# SMART_LOCK_UK.net
KiCad netlist of a schematic drawn in EAGLE
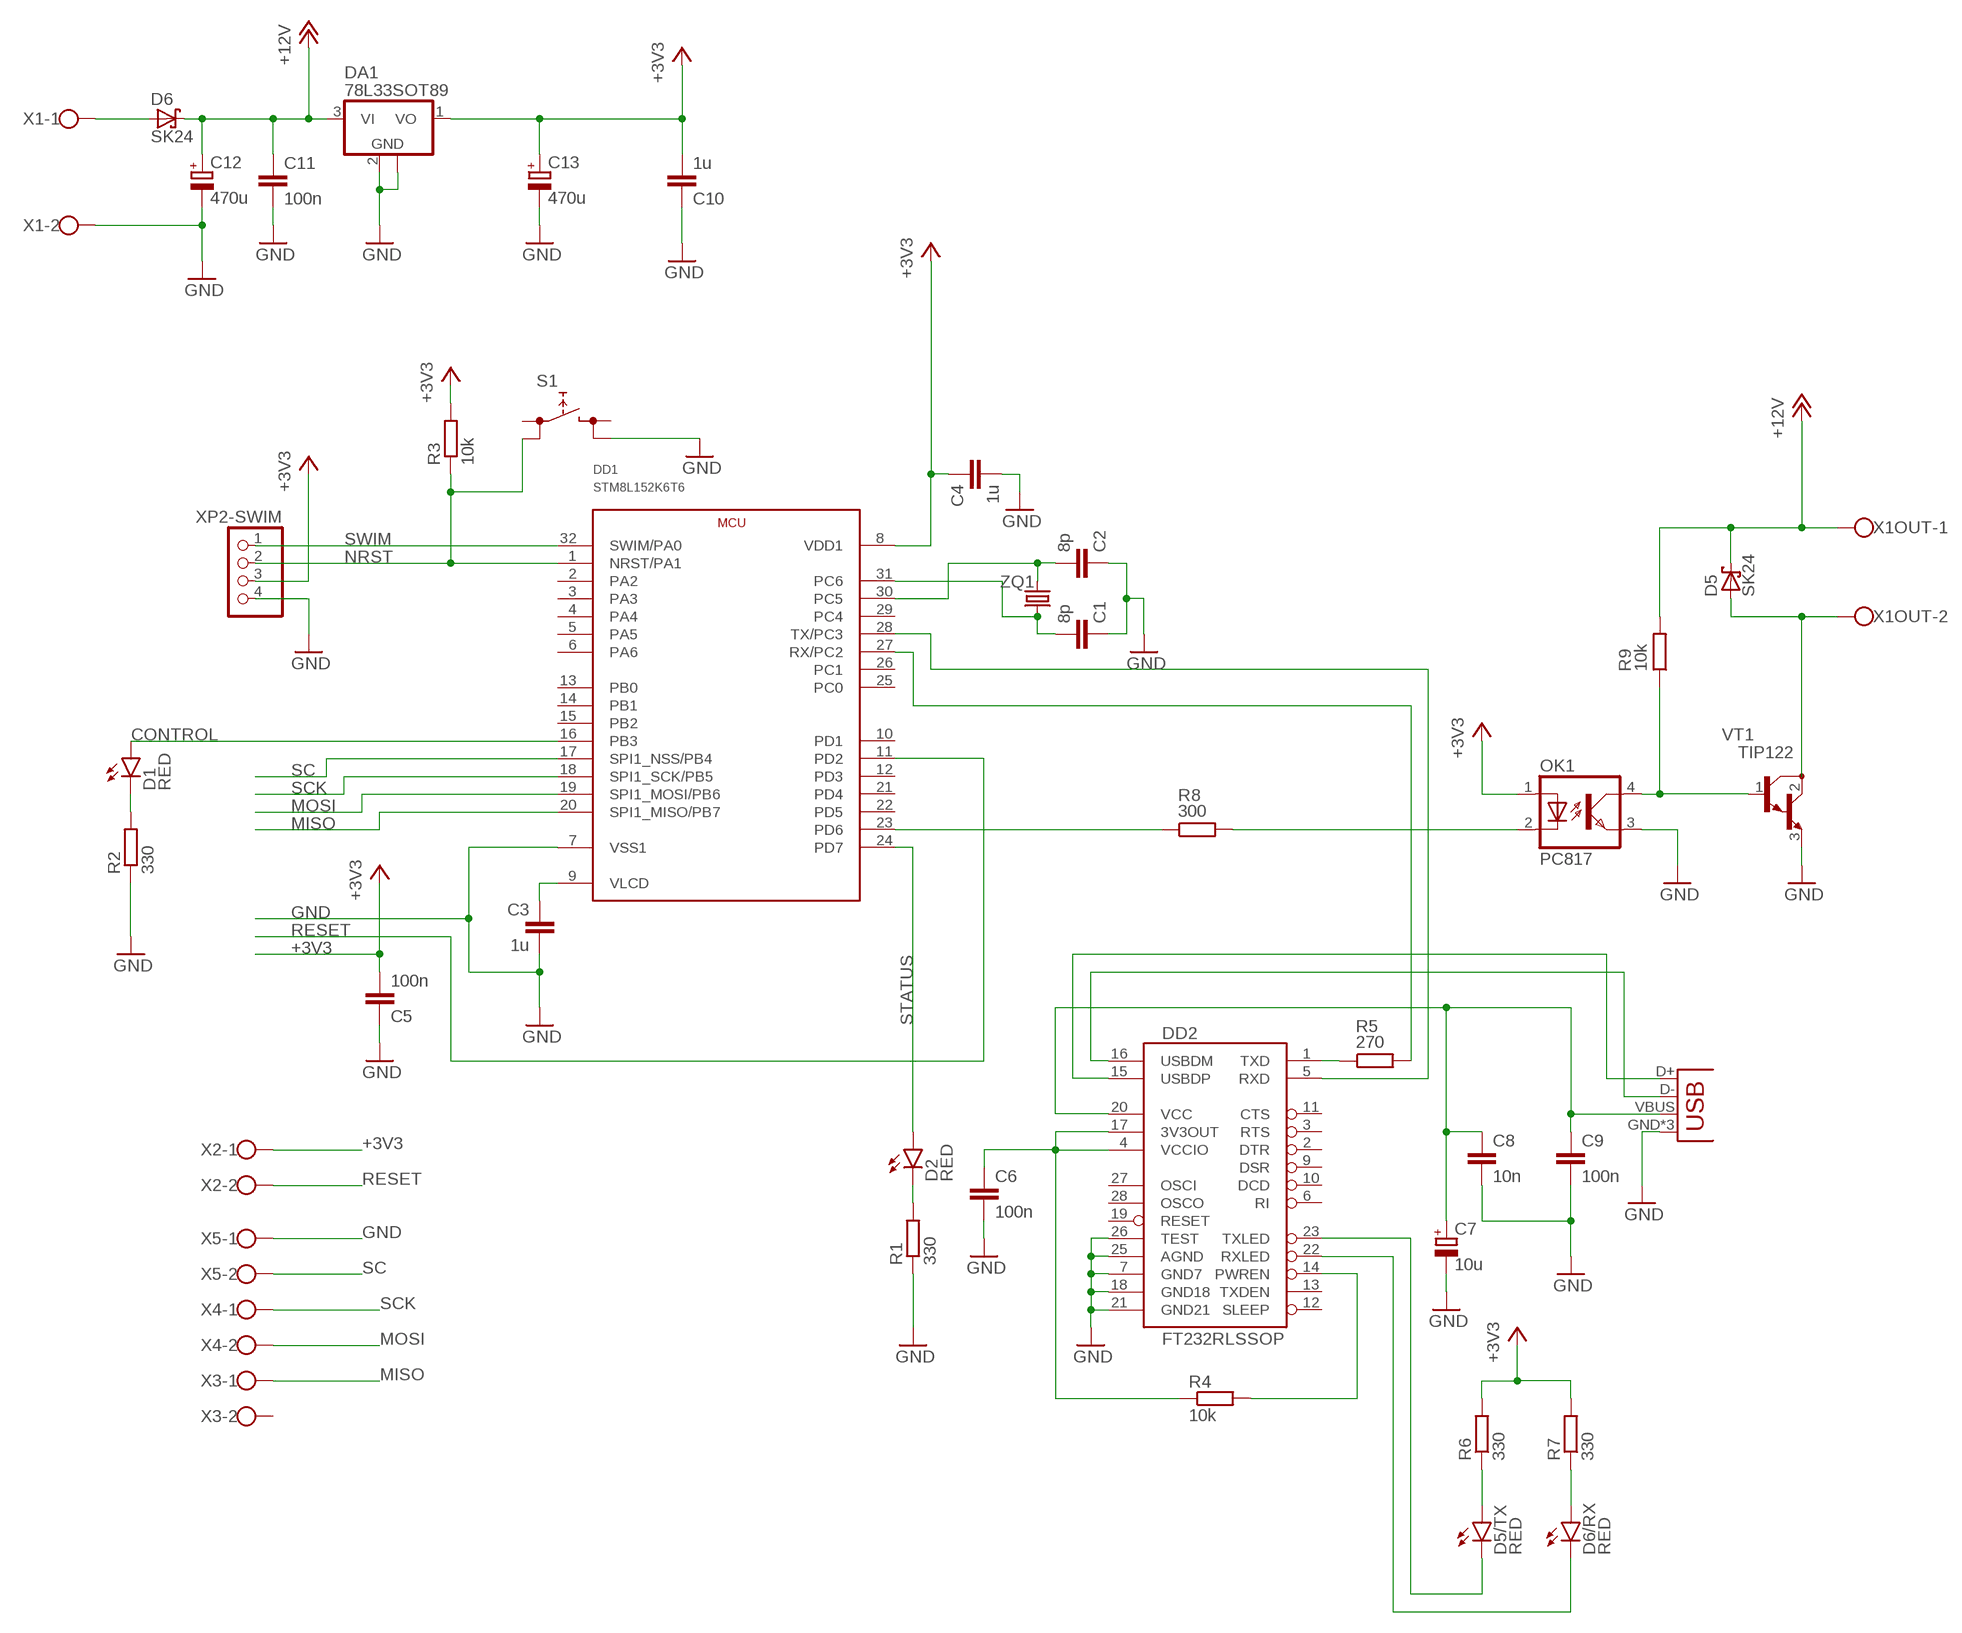
[diagram p0: schematic, sheet 1]

(export (version "E")
  (design (tool "Eeschema 10.0.6"))
  (components
    (comp (ref "C1")
      (value "8p")
      (footprint "eagle-import:C1206")
      (libsource (lib "eagle-import") (part "SMART LOCK UK_C-EUC1206"))
    )
    (comp (ref "C2")
      (value "8p")
      (footprint "eagle-import:C1206")
      (libsource (lib "eagle-import") (part "SMART LOCK UK_C-EUC1206"))
    )
    (comp (ref "C3")
      (value "1u")
      (footprint "eagle-import:C1206")
      (libsource (lib "eagle-import") (part "SMART LOCK UK_C-EUC1206"))
    )
    (comp (ref "C4")
      (value "1u")
      (footprint "eagle-import:C1206")
      (libsource (lib "eagle-import") (part "SMART LOCK UK_C-EUC1206"))
    )
    (comp (ref "C5")
      (value "100n")
      (footprint "eagle-import:C1206")
      (libsource (lib "eagle-import") (part "SMART LOCK UK_C-EUC1206"))
    )
    (comp (ref "C6")
      (value "100n")
      (footprint "eagle-import:C1206")
      (libsource (lib "eagle-import") (part "C-EUC1206"))
    )
    (comp (ref "C7")
      (value "10u")
      (footprint "eagle-import:E2,5-5")
      (libsource (lib "eagle-import") (part "CPOL-EUE2,5-5"))
    )
    (comp (ref "C8")
      (value "10n")
      (footprint "eagle-import:C1206")
      (libsource (lib "eagle-import") (part "C-EUC1206"))
    )
    (comp (ref "C9")
      (value "100n")
      (footprint "eagle-import:C1206")
      (libsource (lib "eagle-import") (part "C-EUC1206"))
    )
    (comp (ref "C10")
      (value "1u")
      (footprint "eagle-import:C1206")
      (libsource (lib "eagle-import") (part "SMART LOCK UK_C-EUC1206"))
    )
    (comp (ref "C11")
      (value "100n")
      (footprint "eagle-import:C1206")
      (libsource (lib "eagle-import") (part "C-EUC1206"))
    )
    (comp (ref "C12")
      (value "470u")
      (footprint "eagle-import:E3,5-8")
      (libsource (lib "eagle-import") (part "CPOL-EUE3,5-8"))
    )
    (comp (ref "C13")
      (value "470u")
      (footprint "eagle-import:E3,5-8")
      (libsource (lib "eagle-import") (part "CPOL-EUE3,5-8"))
    )
    (comp (ref "D1")
      (value "RED")
      (footprint "eagle-import:LED-1206")
      (libsource (lib "eagle-import") (part "LED-RED1206"))
    )
    (comp (ref "D2")
      (value "RED")
      (footprint "eagle-import:LED-1206")
      (libsource (lib "eagle-import") (part "LED-RED1206"))
    )
    (comp (ref "D5")
      (value "SK24")
      (footprint "eagle-import:SMB")
      (libsource (lib "eagle-import") (part "SCHOTTKY-DIODESMD"))
    )
    (comp (ref "D5/TX")
      (value "RED")
      (footprint "eagle-import:LED-1206")
      (libsource (lib "eagle-import") (part "LED-RED1206"))
    )
    (comp (ref "D6")
      (value "SK24")
      (footprint "eagle-import:SMB")
      (libsource (lib "eagle-import") (part "SCHOTTKY-DIODESMD"))
    )
    (comp (ref "D6/RX")
      (value "RED")
      (footprint "eagle-import:LED-1206")
      (libsource (lib "eagle-import") (part "LED-RED1206"))
    )
    (comp (ref "DA1")
      (value "78L33SOT89")
      (footprint "eagle-import:SOT89")
      (libsource (lib "eagle-import") (part "78L33SOT89"))
    )
    (comp (ref "DD1")
      (value "STM8L152K6T6")
      (footprint "eagle-import:LQFP32-7X7")
      (libsource (lib "eagle-import") (part "STM8L152K6T6"))
    )
    (comp (ref "DD2")
      (value "FT232RLSSOP")
      (footprint "eagle-import:SSOP28DB")
      (libsource (lib "eagle-import") (part "FT232RLSSOP"))
    )
    (comp (ref "JP1")
      (value "USB-B")
      (footprint "eagle-import:USB-B-PTH")
      (libsource (lib "eagle-import") (part "USB-B-CROW"))
    )
    (comp (ref "OK1")
      (value "PC817")
      (footprint "eagle-import:DIL04")
      (fields (field (name "MPN") "PC817X4J000F"))
      (libsource (lib "eagle-import") (part "PC817"))
    )
    (comp (ref "R1")
      (value "330")
      (footprint "eagle-import:M1206")
      (libsource (lib "eagle-import") (part "R-EU_LM1206"))
    )
    (comp (ref "R2")
      (value "330")
      (footprint "eagle-import:M1206")
      (libsource (lib "eagle-import") (part "R-EU_LM1206"))
    )
    (comp (ref "R3")
      (value "10k")
      (footprint "eagle-import:M1206")
      (libsource (lib "eagle-import") (part "R-EU_LM1206"))
    )
    (comp (ref "R4")
      (value "10k")
      (footprint "eagle-import:M1206")
      (libsource (lib "eagle-import") (part "R-EUM1206"))
    )
    (comp (ref "R5")
      (value "270")
      (footprint "eagle-import:M1206")
      (libsource (lib "eagle-import") (part "R-EUM1206"))
    )
    (comp (ref "R6")
      (value "330")
      (footprint "eagle-import:M1206")
      (libsource (lib "eagle-import") (part "R-EU_LM1206"))
    )
    (comp (ref "R7")
      (value "330")
      (footprint "eagle-import:M1206")
      (libsource (lib "eagle-import") (part "R-EU_LM1206"))
    )
    (comp (ref "R8")
      (value "300")
      (footprint "eagle-import:M1206")
      (libsource (lib "eagle-import") (part "R-EUM1206"))
    )
    (comp (ref "R9")
      (value "10k")
      (footprint "eagle-import:M1206")
      (libsource (lib "eagle-import") (part "R-EUM1206"))
    )
    (comp (ref "S1")
      (value "TACKT_SW_TH")
      (footprint "eagle-import:TL1105")
      (libsource (lib "eagle-import") (part "TACKT_SW_TH"))
    )
    (comp (ref "VT1")
      (value "TIP122")
      (footprint "eagle-import:TO220")
      (libsource (lib "eagle-import") (part "TIP122"))
    )
    (comp (ref "X1")
      (value "W237-102")
      (footprint "eagle-import:W237-102")
      (fields (field (name "MPN") "237-102"))
      (libsource (lib "eagle-import") (part "W237-102"))
    )
    (comp (ref "X1OUT")
      (value "W237-102")
      (footprint "eagle-import:W237-102")
      (fields (field (name "MPN") "237-102"))
      (libsource (lib "eagle-import") (part "W237-102"))
    )
    (comp (ref "X2")
      (value "DG350-3.5-02P")
      (footprint "eagle-import:DG350-3.5-02P")
      (fields (field (name "MPN") "237-102"))
      (libsource (lib "eagle-import") (part "DG350-3.5-02P"))
    )
    (comp (ref "X3")
      (value "DG350-3.5-02P")
      (footprint "eagle-import:DG350-3.5-02P")
      (fields (field (name "MPN") "237-102"))
      (libsource (lib "eagle-import") (part "DG350-3.5-02P"))
    )
    (comp (ref "X4")
      (value "DG350-3.5-02P")
      (footprint "eagle-import:DG350-3.5-02P")
      (fields (field (name "MPN") "237-102"))
      (libsource (lib "eagle-import") (part "DG350-3.5-02P"))
    )
    (comp (ref "X5")
      (value "DG350-3.5-02P")
      (footprint "eagle-import:DG350-3.5-02P")
      (fields (field (name "MPN") "237-102"))
      (libsource (lib "eagle-import") (part "DG350-3.5-02P"))
    )
    (comp (ref "XP2-SWIM")
      (value "PINHD-1X4")
      (footprint "eagle-import:1X04")
      (libsource (lib "eagle-import") (part "PINHD-1X4"))
    )
    (comp (ref "ZQ1")
      (value "CRYSTAL1MM20SS")
      (footprint "eagle-import:MM20SS")
      (libsource (lib "eagle-import") (part "CRYSTAL1MM20SS"))
    )
  )
  (nets
    (net (code "1") (name "+3V3") (class "Default")
      (node (ref "C10") (pin "2") (pinfunction "2_2") (pintype "passive"))
      (node (ref "C13") (pin "+") (pinfunction "+_+") (pintype "passive"))
      (node (ref "C4") (pin "1") (pinfunction "1_1") (pintype "passive"))
      (node (ref "C5") (pin "2") (pinfunction "2_2") (pintype "passive"))
      (node (ref "DA1") (pin "1") (pinfunction "VO_1") (pintype "passive"))
      (node (ref "DD1") (pin "8") (pinfunction "VDD1_8") (pintype "bidirectional"))
      (node (ref "OK1") (pin "1") (pinfunction "A_1") (pintype "passive"))
      (node (ref "R3") (pin "2") (pinfunction "2_2") (pintype "passive"))
      (node (ref "R6") (pin "2") (pinfunction "2_2") (pintype "passive"))
      (node (ref "R7") (pin "2") (pinfunction "2_2") (pintype "passive"))
      (node (ref "X2") (pin "1") (pinfunction "KL_1") (pintype "passive"))
      (node (ref "XP2-SWIM") (pin "3") (pinfunction "3_3") (pintype "passive"))
    )
    (net (code "2") (name "+12V") (class "Default")
      (node (ref "C11") (pin "1") (pinfunction "1_1") (pintype "passive"))
      (node (ref "C12") (pin "+") (pinfunction "+_+") (pintype "passive"))
      (node (ref "D5") (pin "C") (pinfunction "C_C") (pintype "passive"))
      (node (ref "D6") (pin "C") (pinfunction "C_C") (pintype "passive"))
      (node (ref "DA1") (pin "3") (pinfunction "VI_3") (pintype "input"))
      (node (ref "R9") (pin "2") (pinfunction "2_2") (pintype "passive"))
      (node (ref "X1OUT") (pin "1") (pinfunction "KL_1") (pintype "passive"))
    )
    (net (code "3") (name "/CONTROL") (class "Default")
      (node (ref "D1") (pin "A") (pinfunction "A_A") (pintype "passive"))
      (node (ref "DD1") (pin "16") (pinfunction "PB3_16") (pintype "bidirectional"))
    )
    (net (code "4") (name "/MISO") (class "Default")
      (node (ref "DD1") (pin "20") (pinfunction "SPI1_MISO/PB7_20") (pintype "bidirectional"))
      (node (ref "X3") (pin "1") (pinfunction "KL_1") (pintype "passive"))
    )
    (net (code "5") (name "/MOSI") (class "Default")
      (node (ref "DD1") (pin "19") (pinfunction "SPI1_MOSI/PB6_19") (pintype "bidirectional"))
      (node (ref "X4") (pin "2") (pinfunction "KL_2") (pintype "passive"))
    )
    (net (code "6") (name "/NRST") (class "Default")
      (node (ref "DD1") (pin "1") (pinfunction "NRST/PA1_1") (pintype "bidirectional"))
      (node (ref "R3") (pin "1") (pinfunction "1_1") (pintype "passive"))
      (node (ref "S1") (pin "3") (pinfunction "0_3") (pintype "passive"))
      (node (ref "XP2-SWIM") (pin "2") (pinfunction "2_2") (pintype "passive"))
    )
    (net (code "7") (name "/RESET") (class "Default")
      (node (ref "DD1") (pin "11") (pinfunction "PD2_11") (pintype "bidirectional"))
      (node (ref "X2") (pin "2") (pinfunction "KL_2") (pintype "passive"))
    )
    (net (code "8") (name "/SC") (class "Default")
      (node (ref "DD1") (pin "17") (pinfunction "SPI1_NSS/PB4_17") (pintype "bidirectional"))
      (node (ref "X5") (pin "2") (pinfunction "KL_2") (pintype "passive"))
    )
    (net (code "9") (name "/SCK") (class "Default")
      (node (ref "DD1") (pin "18") (pinfunction "SPI1_SCK/PB5_18") (pintype "bidirectional"))
      (node (ref "X4") (pin "1") (pinfunction "KL_1") (pintype "passive"))
    )
    (net (code "10") (name "/STATUS") (class "Default")
      (node (ref "D2") (pin "A") (pinfunction "A_A") (pintype "passive"))
      (node (ref "DD1") (pin "24") (pinfunction "PD7_24") (pintype "bidirectional"))
    )
    (net (code "11") (name "/SWIM") (class "Default")
      (node (ref "DD1") (pin "32") (pinfunction "SWIM/PA0_32") (pintype "bidirectional"))
      (node (ref "XP2-SWIM") (pin "1") (pinfunction "1_1") (pintype "passive"))
    )
    (net (code "12") (name "GND") (class "Default")
      (node (ref "C1") (pin "1") (pinfunction "1_1") (pintype "passive"))
      (node (ref "C10") (pin "1") (pinfunction "1_1") (pintype "passive"))
      (node (ref "C11") (pin "2") (pinfunction "2_2") (pintype "passive"))
      (node (ref "C12") (pin "-") (pinfunction "-_-") (pintype "passive"))
      (node (ref "C13") (pin "-") (pinfunction "-_-") (pintype "passive"))
      (node (ref "C2") (pin "1") (pinfunction "1_1") (pintype "passive"))
      (node (ref "C3") (pin "2") (pinfunction "2_2") (pintype "passive"))
      (node (ref "C4") (pin "2") (pinfunction "2_2") (pintype "passive"))
      (node (ref "C5") (pin "1") (pinfunction "1_1") (pintype "passive"))
      (node (ref "C6") (pin "2") (pinfunction "2_2") (pintype "passive"))
      (node (ref "C7") (pin "-") (pinfunction "-_-") (pintype "passive"))
      (node (ref "C8") (pin "2") (pinfunction "2_2") (pintype "passive"))
      (node (ref "C9") (pin "2") (pinfunction "2_2") (pintype "passive"))
      (node (ref "DA1") (pin "2") (pinfunction "GND_2") (pintype "passive"))
      (node (ref "DA1") (pin "2@1") (pinfunction "GND_2@1") (pintype "passive"))
      (node (ref "DD1") (pin "7") (pinfunction "VSS1_7") (pintype "bidirectional"))
      (node (ref "DD2") (pin "18") (pinfunction "GND18_18") (pintype "power_in"))
      (node (ref "DD2") (pin "21") (pinfunction "GND21_21") (pintype "power_in"))
      (node (ref "DD2") (pin "25") (pinfunction "AGND_25") (pintype "power_in"))
      (node (ref "DD2") (pin "26") (pinfunction "TEST_26") (pintype "input"))
      (node (ref "DD2") (pin "7") (pinfunction "GND7_7") (pintype "power_in"))
      (node (ref "JP1") (pin "GND") (pinfunction "GND_GND") (pintype "bidirectional"))
      (node (ref "JP1") (pin "S1") (pinfunction "GND_S1") (pintype "bidirectional"))
      (node (ref "JP1") (pin "S2") (pinfunction "GND_S2") (pintype "bidirectional"))
      (node (ref "OK1") (pin "3") (pinfunction "EMIT_3") (pintype "passive"))
      (node (ref "R1") (pin "1") (pinfunction "1_1") (pintype "passive"))
      (node (ref "R2") (pin "1") (pinfunction "1_1") (pintype "passive"))
      (node (ref "S1") (pin "4") (pinfunction "1_4") (pintype "passive"))
      (node (ref "VT1") (pin "3") (pinfunction "E_3") (pintype "passive"))
      (node (ref "X1") (pin "2") (pinfunction "KL_2") (pintype "passive"))
      (node (ref "X5") (pin "1") (pinfunction "KL_1") (pintype "passive"))
      (node (ref "XP2-SWIM") (pin "4") (pinfunction "4_4") (pintype "passive"))
    )
    (net (code "13") (name "Net-(D1-PadC)") (class "Default")
      (node (ref "D1") (pin "C") (pinfunction "C_C") (pintype "passive"))
      (node (ref "R2") (pin "2") (pinfunction "2_2") (pintype "passive"))
    )
    (net (code "14") (name "Net-(D2-PadC)") (class "Default")
      (node (ref "D2") (pin "C") (pinfunction "C_C") (pintype "passive"))
      (node (ref "R1") (pin "2") (pinfunction "2_2") (pintype "passive"))
    )
    (net (code "15") (name "Net-(D5/TX-PadA)") (class "Default")
      (node (ref "D5/TX") (pin "A") (pinfunction "A_A") (pintype "passive"))
      (node (ref "R6") (pin "1") (pinfunction "1_1") (pintype "passive"))
    )
    (net (code "16") (name "Net-(D6/RX-PadA)") (class "Default")
      (node (ref "D6/RX") (pin "A") (pinfunction "A_A") (pintype "passive"))
      (node (ref "R7") (pin "1") (pinfunction "1_1") (pintype "passive"))
    )
    (net (code "17") (name "Net-(DD1-PC5)") (class "Default")
      (node (ref "C2") (pin "2") (pinfunction "2_2") (pintype "passive"))
      (node (ref "DD1") (pin "30") (pinfunction "PC5_30") (pintype "bidirectional"))
      (node (ref "ZQ1") (pin "4") (pinfunction "2_4") (pintype "passive"))
    )
    (net (code "18") (name "Net-(DD1-PC6)") (class "Default")
      (node (ref "C1") (pin "2") (pinfunction "2_2") (pintype "passive"))
      (node (ref "DD1") (pin "31") (pinfunction "PC6_31") (pintype "bidirectional"))
      (node (ref "ZQ1") (pin "1") (pinfunction "1_1") (pintype "passive"))
    )
    (net (code "19") (name "Net-(DD1-PD6)") (class "Default")
      (node (ref "DD1") (pin "23") (pinfunction "PD6_23") (pintype "bidirectional"))
      (node (ref "R8") (pin "1") (pinfunction "1_1") (pintype "passive"))
    )
    (net (code "20") (name "Net-(DD1-RX{slash}PC2)") (class "Default")
      (node (ref "DD1") (pin "27") (pinfunction "RX/PC2_27") (pintype "bidirectional"))
      (node (ref "R5") (pin "2") (pinfunction "2_2") (pintype "passive"))
    )
    (net (code "21") (name "Net-(DD1-TX{slash}PC3)") (class "Default")
      (node (ref "DD1") (pin "28") (pinfunction "TX/PC3_28") (pintype "bidirectional"))
      (node (ref "DD2") (pin "5") (pinfunction "RXD_5") (pintype "input"))
    )
    (net (code "22") (name "Net-(DD1-VLCD)") (class "Default")
      (node (ref "C3") (pin "1") (pinfunction "1_1") (pintype "passive"))
      (node (ref "DD1") (pin "9") (pinfunction "VLCD_9") (pintype "bidirectional"))
    )
    (net (code "23") (name "Net-(DD2-3V3OUT)") (class "Default")
      (node (ref "C6") (pin "1") (pinfunction "1_1") (pintype "passive"))
      (node (ref "DD2") (pin "17") (pinfunction "3V3OUT_17") (pintype "output"))
      (node (ref "DD2") (pin "4") (pinfunction "VCCIO_4") (pintype "power_in"))
      (node (ref "R4") (pin "1") (pinfunction "1_1") (pintype "passive"))
    )
    (net (code "24") (name "Net-(DD2-PWREN)") (class "Default")
      (node (ref "DD2") (pin "14") (pinfunction "PWREN_14") (pintype "input"))
      (node (ref "R4") (pin "2") (pinfunction "2_2") (pintype "passive"))
    )
    (net (code "25") (name "Net-(DD2-RXLED)") (class "Default")
      (node (ref "D6/RX") (pin "C") (pinfunction "C_C") (pintype "passive"))
      (node (ref "DD2") (pin "22") (pinfunction "RXLED_22") (pintype "input"))
    )
    (net (code "26") (name "Net-(DD2-TXD)") (class "Default")
      (node (ref "DD2") (pin "1") (pinfunction "TXD_1") (pintype "output"))
      (node (ref "R5") (pin "1") (pinfunction "1_1") (pintype "passive"))
    )
    (net (code "27") (name "Net-(DD2-TXLED)") (class "Default")
      (node (ref "D5/TX") (pin "C") (pinfunction "C_C") (pintype "passive"))
      (node (ref "DD2") (pin "23") (pinfunction "TXLED_23") (pintype "input"))
    )
    (net (code "28") (name "Net-(DD2-USBDM)") (class "Default")
      (node (ref "DD2") (pin "16") (pinfunction "USBDM_16") (pintype "bidirectional"))
      (node (ref "JP1") (pin "D-") (pinfunction "D-_D-") (pintype "bidirectional"))
    )
    (net (code "29") (name "Net-(DD2-USBDP)") (class "Default")
      (node (ref "DD2") (pin "15") (pinfunction "USBDP_15") (pintype "bidirectional"))
      (node (ref "JP1") (pin "D+") (pinfunction "D+_D+") (pintype "bidirectional"))
    )
    (net (code "30") (name "Net-(DD2-VCC)") (class "Default")
      (node (ref "C7") (pin "+") (pinfunction "+_+") (pintype "passive"))
      (node (ref "C8") (pin "1") (pinfunction "1_1") (pintype "passive"))
      (node (ref "C9") (pin "1") (pinfunction "1_1") (pintype "passive"))
      (node (ref "DD2") (pin "20") (pinfunction "VCC_20") (pintype "power_in"))
      (node (ref "JP1") (pin "VBUS") (pinfunction "VBUS_VBUS") (pintype "bidirectional"))
    )
    (net (code "31") (name "Net-(OK1-C)") (class "Default")
      (node (ref "OK1") (pin "2") (pinfunction "C_2") (pintype "passive"))
      (node (ref "R8") (pin "2") (pinfunction "2_2") (pintype "passive"))
    )
    (net (code "32") (name "Net-(OK1-COL)") (class "Default")
      (node (ref "OK1") (pin "4") (pinfunction "COL_4") (pintype "passive"))
      (node (ref "R9") (pin "1") (pinfunction "1_1") (pintype "passive"))
      (node (ref "VT1") (pin "1") (pinfunction "B_1") (pintype "passive"))
    )
    (net (code "33") (name "Net-(VT1-C)") (class "Default")
      (node (ref "D5") (pin "A") (pinfunction "A_A") (pintype "passive"))
      (node (ref "VT1") (pin "2") (pinfunction "C_2") (pintype "passive"))
      (node (ref "X1OUT") (pin "2") (pinfunction "KL_2") (pintype "passive"))
    )
    (net (code "34") (name "Net-(X1A-KL)") (class "Default")
      (node (ref "D6") (pin "A") (pinfunction "A_A") (pintype "passive"))
      (node (ref "X1") (pin "1") (pinfunction "KL_1") (pintype "passive"))
    )
    (net (code "35") (name "unconnected-(DD1-PA2-Pad2)") (class "Default")
      (node (ref "DD1") (pin "2") (pinfunction "PA2_2") (pintype "bidirectional"))
    )
    (net (code "36") (name "unconnected-(DD1-PA3-Pad3)") (class "Default")
      (node (ref "DD1") (pin "3") (pinfunction "PA3_3") (pintype "bidirectional"))
    )
    (net (code "37") (name "unconnected-(DD1-PA4-Pad4)") (class "Default")
      (node (ref "DD1") (pin "4") (pinfunction "PA4_4") (pintype "bidirectional"))
    )
    (net (code "38") (name "unconnected-(DD1-PA5-Pad5)") (class "Default")
      (node (ref "DD1") (pin "5") (pinfunction "PA5_5") (pintype "bidirectional"))
    )
    (net (code "39") (name "unconnected-(DD1-PA6-Pad6)") (class "Default")
      (node (ref "DD1") (pin "6") (pinfunction "PA6_6") (pintype "bidirectional"))
    )
    (net (code "40") (name "unconnected-(DD1-PB0-Pad13)") (class "Default")
      (node (ref "DD1") (pin "13") (pinfunction "PB0_13") (pintype "bidirectional"))
    )
    (net (code "41") (name "unconnected-(DD1-PB1-Pad14)") (class "Default")
      (node (ref "DD1") (pin "14") (pinfunction "PB1_14") (pintype "bidirectional"))
    )
    (net (code "42") (name "unconnected-(DD1-PB2-Pad15)") (class "Default")
      (node (ref "DD1") (pin "15") (pinfunction "PB2_15") (pintype "bidirectional"))
    )
    (net (code "43") (name "unconnected-(DD1-PC0-Pad25)") (class "Default")
      (node (ref "DD1") (pin "25") (pinfunction "PC0_25") (pintype "bidirectional"))
    )
    (net (code "44") (name "unconnected-(DD1-PC1-Pad26)") (class "Default")
      (node (ref "DD1") (pin "26") (pinfunction "PC1_26") (pintype "bidirectional"))
    )
    (net (code "45") (name "unconnected-(DD1-PC4-Pad29)") (class "Default")
      (node (ref "DD1") (pin "29") (pinfunction "PC4_29") (pintype "bidirectional"))
    )
    (net (code "46") (name "unconnected-(DD1-PD1-Pad10)") (class "Default")
      (node (ref "DD1") (pin "10") (pinfunction "PD1_10") (pintype "bidirectional"))
    )
    (net (code "47") (name "unconnected-(DD1-PD3-Pad12)") (class "Default")
      (node (ref "DD1") (pin "12") (pinfunction "PD3_12") (pintype "bidirectional"))
    )
    (net (code "48") (name "unconnected-(DD1-PD4-Pad21)") (class "Default")
      (node (ref "DD1") (pin "21") (pinfunction "PD4_21") (pintype "bidirectional"))
    )
    (net (code "49") (name "unconnected-(DD1-PD5-Pad22)") (class "Default")
      (node (ref "DD1") (pin "22") (pinfunction "PD5_22") (pintype "bidirectional"))
    )
    (net (code "50") (name "unconnected-(DD2-CTS-Pad11)") (class "Default")
      (node (ref "DD2") (pin "11") (pinfunction "CTS_11") (pintype "input"))
    )
    (net (code "51") (name "unconnected-(DD2-DCD-Pad10)") (class "Default")
      (node (ref "DD2") (pin "10") (pinfunction "DCD_10") (pintype "input"))
    )
    (net (code "52") (name "unconnected-(DD2-DSR-Pad9)") (class "Default")
      (node (ref "DD2") (pin "9") (pinfunction "DSR_9") (pintype "input"))
    )
    (net (code "53") (name "unconnected-(DD2-DTR-Pad2)") (class "Default")
      (node (ref "DD2") (pin "2") (pinfunction "DTR_2") (pintype "output"))
    )
    (net (code "54") (name "unconnected-(DD2-OSCI-Pad27)") (class "Default")
      (node (ref "DD2") (pin "27") (pinfunction "OSCI_27") (pintype "input"))
    )
    (net (code "55") (name "unconnected-(DD2-OSCO-Pad28)") (class "Default")
      (node (ref "DD2") (pin "28") (pinfunction "OSCO_28") (pintype "output"))
    )
    (net (code "56") (name "unconnected-(DD2-RESET-Pad19)") (class "Default")
      (node (ref "DD2") (pin "19") (pinfunction "RESET_19") (pintype "input"))
    )
    (net (code "57") (name "unconnected-(DD2-RI-Pad6)") (class "Default")
      (node (ref "DD2") (pin "6") (pinfunction "RI_6") (pintype "input"))
    )
    (net (code "58") (name "unconnected-(DD2-RTS-Pad3)") (class "Default")
      (node (ref "DD2") (pin "3") (pinfunction "RTS_3") (pintype "output"))
    )
    (net (code "59") (name "unconnected-(DD2-SLEEP-Pad12)") (class "Default")
      (node (ref "DD2") (pin "12") (pinfunction "SLEEP_12") (pintype "input"))
    )
    (net (code "60") (name "unconnected-(DD2-TXDEN-Pad13)") (class "Default")
      (node (ref "DD2") (pin "13") (pinfunction "TXDEN_13") (pintype "input"))
    )
    (net (code "61") (name "unconnected-(S1-0-Pad1)") (class "Default")
      (node (ref "S1") (pin "1") (pinfunction "0_1") (pintype "passive"))
    )
    (net (code "62") (name "unconnected-(S1-1-Pad2)") (class "Default")
      (node (ref "S1") (pin "2") (pinfunction "1_2") (pintype "passive"))
    )
    (net (code "63") (name "unconnected-(X3B-KL-Pad2)") (class "Default")
      (node (ref "X3") (pin "2") (pinfunction "KL_2") (pintype "passive"))
    )
  )
)
